# DD2090_4CAM_FFC_MIPI_2LANE_CAM.net
KiCad netlist of a schematic drawn in Altium Designer
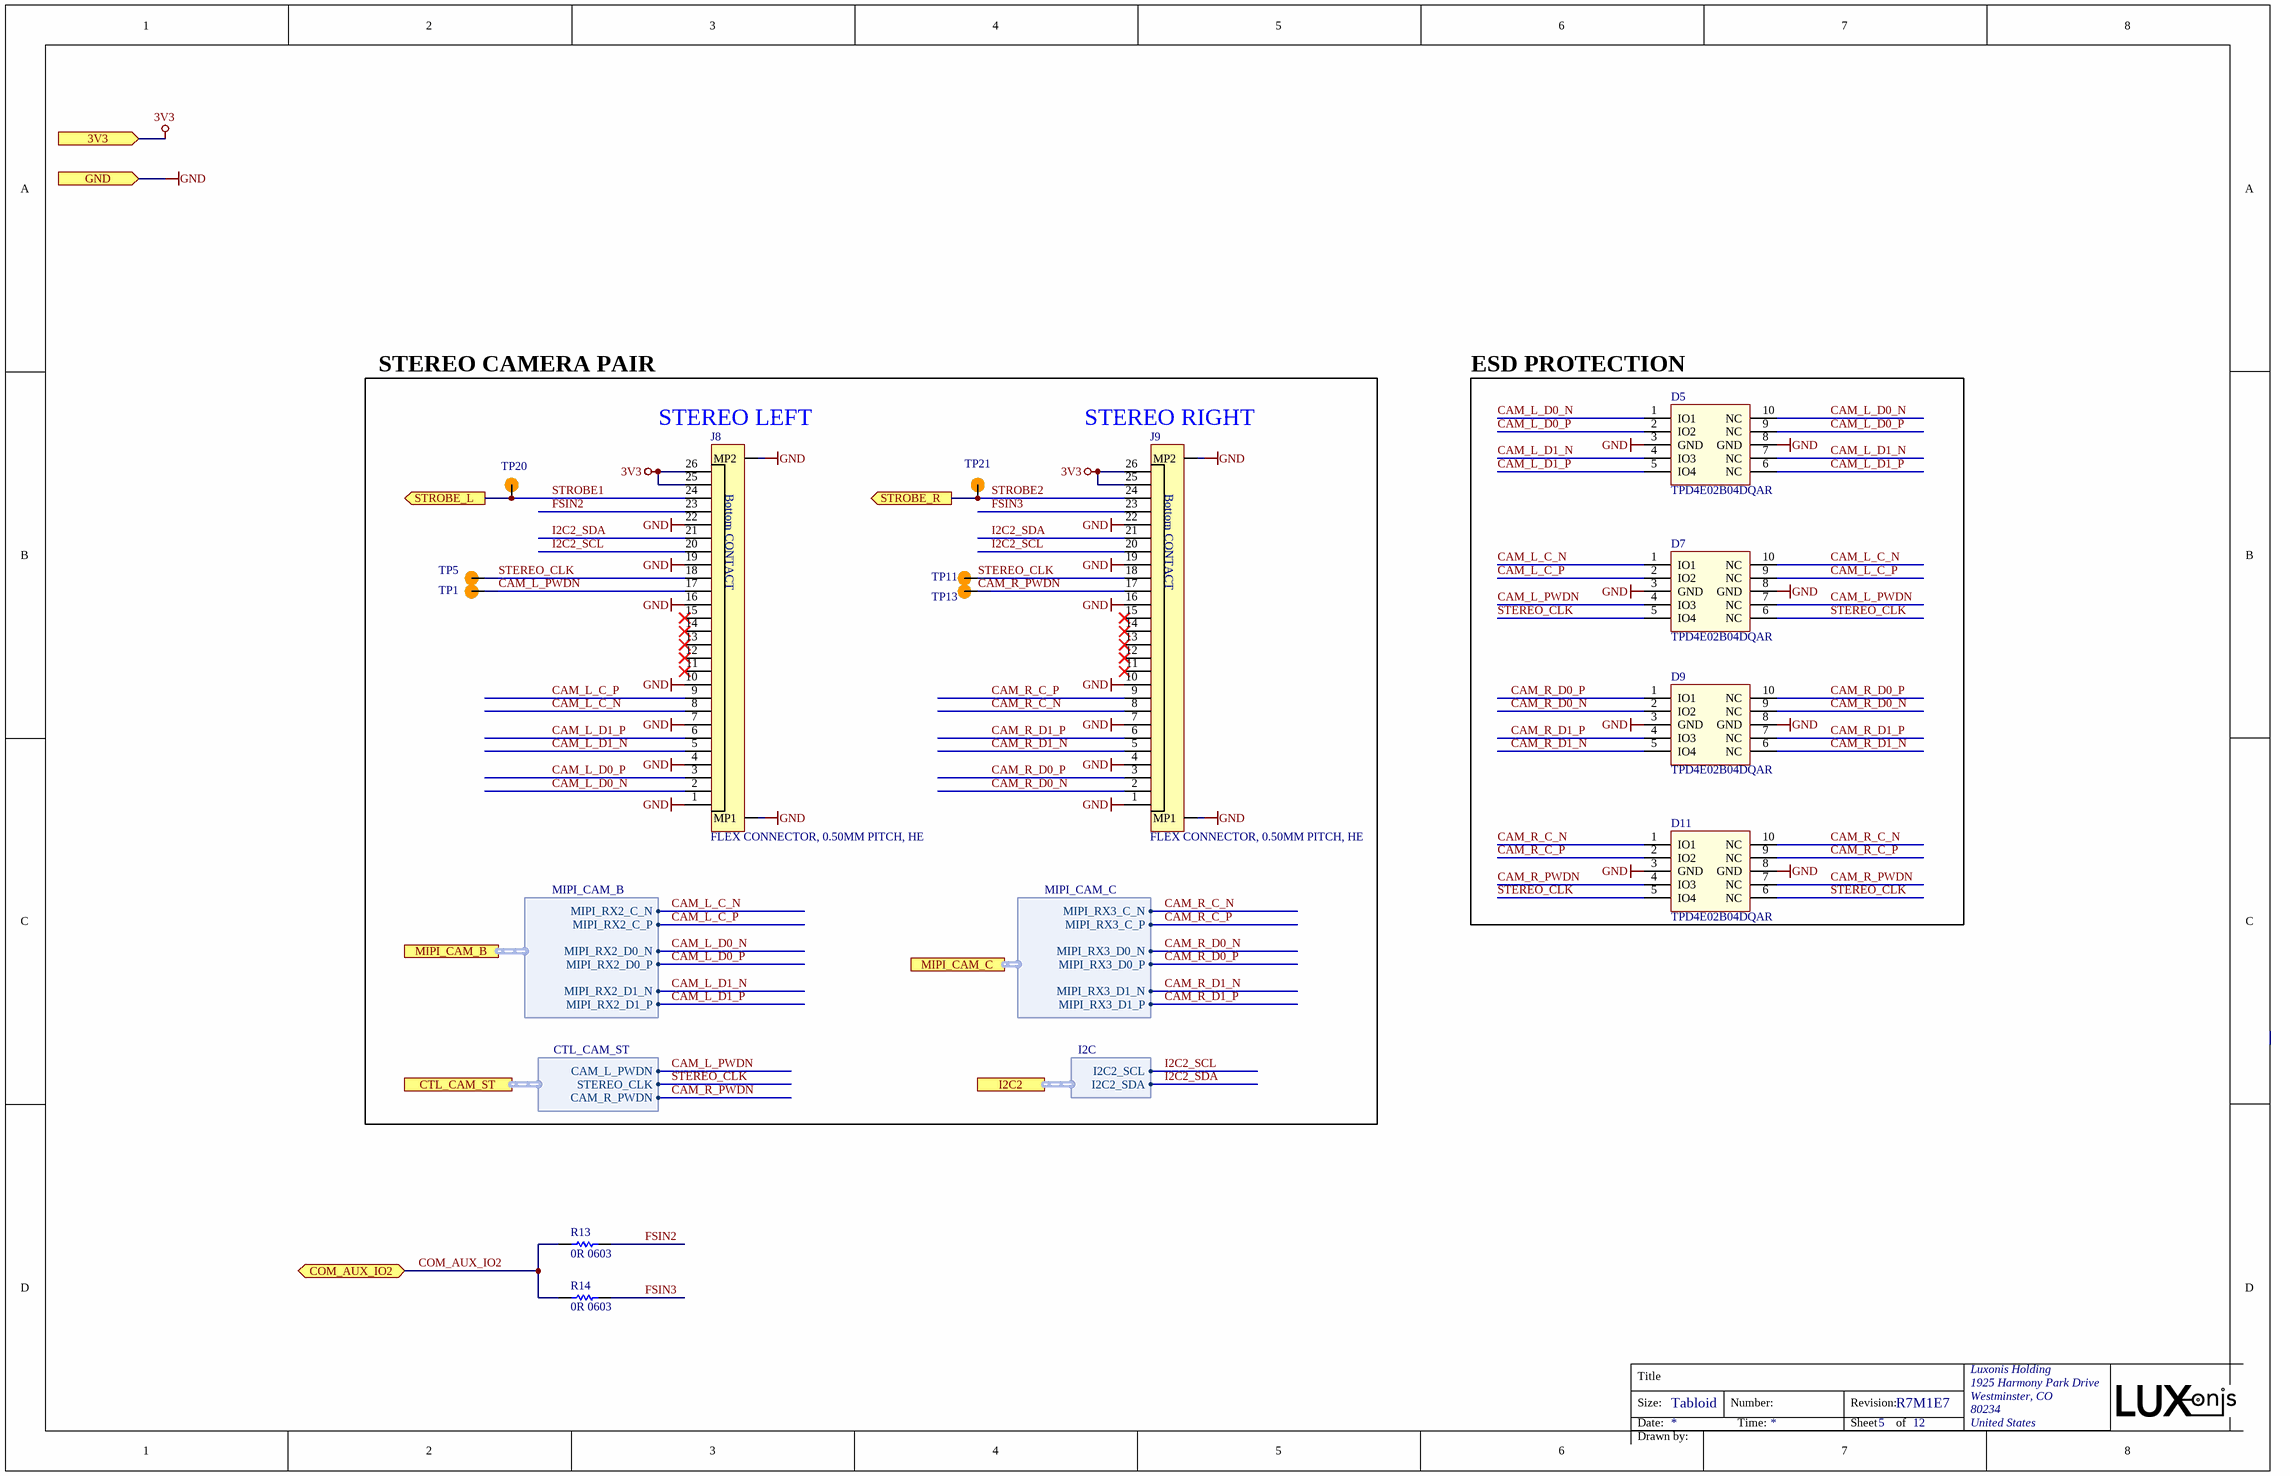
[diagram p0: DD2090_4CAM_FFC_MIPI_2LANE_CAM.SchDoc]

(export (version "E")
  (design (tool "Eeschema 10.0.6"))
  (components
    (comp (ref "D5")
      (value "TPD4E02B04DQAR")
      (footprint "LuxonisMaster:TPD4E02B04DQAR")
      (libsource (lib "LuxonisMaster") (part "TPD4E02B04DQAR"))
    )
    (comp (ref "D7")
      (value "TPD4E02B04DQAR")
      (footprint "LuxonisMaster:TPD4E02B04DQAR")
      (libsource (lib "LuxonisMaster") (part "TPD4E02B04DQAR"))
    )
    (comp (ref "D9")
      (value "TPD4E02B04DQAR")
      (footprint "LuxonisMaster:TPD4E02B04DQAR")
      (libsource (lib "LuxonisMaster") (part "TPD4E02B04DQAR"))
    )
    (comp (ref "D11")
      (value "TPD4E02B04DQAR")
      (footprint "LuxonisMaster:TPD4E02B04DQAR")
      (libsource (lib "LuxonisMaster") (part "TPD4E02B04DQAR"))
    )
    (comp (ref "J8")
      (value "FLEX CONNECTOR, 0.50MM PITCH, HE")
      (footprint "DM1090FFC:F32R-1A7H1-11026")
      (description "26 Position FFC, FPC Connector Contacts, Bottom 0.020\" (0.50mm) Surface Mount, Right Angle")
      (libsource (lib "DM1090FFC") (part "F32R-1A7H1-11026"))
    )
    (comp (ref "J9")
      (value "FLEX CONNECTOR, 0.50MM PITCH, HE")
      (footprint "DM1090FFC:F32R-1A7H1-11026")
      (description "26 Position FFC, FPC Connector Contacts, Bottom 0.020\" (0.50mm) Surface Mount, Right Angle")
      (libsource (lib "DM1090FFC") (part "F32R-1A7H1-11026"))
    )
    (comp (ref "R13")
      (value "0R 0603")
      (footprint "RES_Altium_Vault_Generic:RESC0603(1608)_N")
      (fields (field (name "TOLERANCE") "5%"))
      (libsource (lib "LuxonisMaster") (part "CRCW06030000Z0EA"))
    )
    (comp (ref "R14")
      (value "0R 0603")
      (footprint "RES_Altium_Vault_Generic:RESC0603(1608)_N")
      (fields (field (name "TOLERANCE") "5%"))
      (libsource (lib "LuxonisMaster") (part "CRCW06030000Z0EA"))
    )
    (comp (ref "TP1")
      (value "TP100_200_NS")
      (footprint "LuxonisMaster:TP100_200_NS")
      (libsource (lib "LuxonisMaster") (part "TEST_POINT"))
    )
    (comp (ref "TP5")
      (value "TP100_200_NS")
      (footprint "LuxonisMaster:TP100_200_NS")
      (libsource (lib "LuxonisMaster") (part "TEST_POINT"))
    )
    (comp (ref "TP11")
      (value "TP100_200_NS")
      (footprint "LuxonisMaster:TP100_200_NS")
      (libsource (lib "LuxonisMaster") (part "TEST_POINT"))
    )
    (comp (ref "TP13")
      (value "TP100_200_NS")
      (footprint "LuxonisMaster:TP100_200_NS")
      (libsource (lib "LuxonisMaster") (part "TEST_POINT"))
    )
    (comp (ref "TP20")
      (value "TP100_200_NS")
      (footprint "LuxonisMaster:TP100_200_NS")
      (libsource (lib "LuxonisMaster") (part "TEST_POINT"))
    )
    (comp (ref "TP21")
      (value "TP100_200_NS")
      (footprint "LuxonisMaster:TP100_200_NS")
      (libsource (lib "LuxonisMaster") (part "TEST_POINT"))
    )
  )
  (nets
    (net (code "5") (name "/CAM_L_C_N") (class "Default")
      (node (ref "D7") (pin "1") (pinfunction "IO1_1") (pintype "passive"))
      (node (ref "D7") (pin "10") (pinfunction "NC_10") (pintype "passive"))
      (node (ref "J8") (pin "8") (pinfunction "8_8") (pintype "passive"))
    )
    (net (code "6") (name "/CAM_L_C_P") (class "Default")
      (node (ref "D7") (pin "2") (pinfunction "IO2_2") (pintype "passive"))
      (node (ref "D7") (pin "9") (pinfunction "NC_9") (pintype "passive"))
      (node (ref "J8") (pin "9") (pinfunction "9_9") (pintype "passive"))
    )
    (net (code "7") (name "/CAM_L_D0_N") (class "Default")
      (node (ref "D5") (pin "1") (pinfunction "IO1_1") (pintype "passive"))
      (node (ref "D5") (pin "10") (pinfunction "NC_10") (pintype "passive"))
      (node (ref "J8") (pin "2") (pinfunction "2_2") (pintype "passive"))
    )
    (net (code "8") (name "/CAM_L_D0_P") (class "Default")
      (node (ref "D5") (pin "2") (pinfunction "IO2_2") (pintype "passive"))
      (node (ref "D5") (pin "9") (pinfunction "NC_9") (pintype "passive"))
      (node (ref "J8") (pin "3") (pinfunction "3_3") (pintype "passive"))
    )
    (net (code "9") (name "/CAM_L_D1_N") (class "Default")
      (node (ref "D5") (pin "4") (pinfunction "IO3_4") (pintype "passive"))
      (node (ref "D5") (pin "7") (pinfunction "NC_7") (pintype "passive"))
      (node (ref "J8") (pin "5") (pinfunction "5_5") (pintype "passive"))
    )
    (net (code "10") (name "/CAM_L_D1_P") (class "Default")
      (node (ref "D5") (pin "5") (pinfunction "IO4_5") (pintype "passive"))
      (node (ref "D5") (pin "6") (pinfunction "NC_6") (pintype "passive"))
      (node (ref "J8") (pin "6") (pinfunction "6_6") (pintype "passive"))
    )
    (net (code "11") (name "/CAM_L_PWDN") (class "Default")
      (node (ref "D7") (pin "4") (pinfunction "IO3_4") (pintype "passive"))
      (node (ref "D7") (pin "7") (pinfunction "NC_7") (pintype "passive"))
      (node (ref "J8") (pin "17") (pinfunction "17_17") (pintype "passive"))
      (node (ref "TP1") (pin "1") (pintype "passive"))
    )
    (net (code "12") (name "/CAM_R_C_N") (class "Default")
      (node (ref "D11") (pin "1") (pinfunction "IO1_1") (pintype "passive"))
      (node (ref "D11") (pin "10") (pinfunction "NC_10") (pintype "passive"))
      (node (ref "J9") (pin "8") (pinfunction "8_8") (pintype "passive"))
    )
    (net (code "13") (name "/CAM_R_C_P") (class "Default")
      (node (ref "D11") (pin "2") (pinfunction "IO2_2") (pintype "passive"))
      (node (ref "D11") (pin "9") (pinfunction "NC_9") (pintype "passive"))
      (node (ref "J9") (pin "9") (pinfunction "9_9") (pintype "passive"))
    )
    (net (code "14") (name "/CAM_R_D0_N") (class "Default")
      (node (ref "D9") (pin "2") (pinfunction "IO2_2") (pintype "passive"))
      (node (ref "D9") (pin "9") (pinfunction "NC_9") (pintype "passive"))
      (node (ref "J9") (pin "2") (pinfunction "2_2") (pintype "passive"))
    )
    (net (code "15") (name "/CAM_R_D0_P") (class "Default")
      (node (ref "D9") (pin "1") (pinfunction "IO1_1") (pintype "passive"))
      (node (ref "D9") (pin "10") (pinfunction "NC_10") (pintype "passive"))
      (node (ref "J9") (pin "3") (pinfunction "3_3") (pintype "passive"))
    )
    (net (code "16") (name "/CAM_R_D1_N") (class "Default")
      (node (ref "D9") (pin "5") (pinfunction "IO4_5") (pintype "passive"))
      (node (ref "D9") (pin "6") (pinfunction "NC_6") (pintype "passive"))
      (node (ref "J9") (pin "5") (pinfunction "5_5") (pintype "passive"))
    )
    (net (code "17") (name "/CAM_R_D1_P") (class "Default")
      (node (ref "D9") (pin "4") (pinfunction "IO3_4") (pintype "passive"))
      (node (ref "D9") (pin "7") (pinfunction "NC_7") (pintype "passive"))
      (node (ref "J9") (pin "6") (pinfunction "6_6") (pintype "passive"))
    )
    (net (code "18") (name "/CAM_R_PWDN") (class "Default")
      (node (ref "D11") (pin "4") (pinfunction "IO3_4") (pintype "passive"))
      (node (ref "D11") (pin "7") (pinfunction "NC_7") (pintype "passive"))
      (node (ref "J9") (pin "17") (pinfunction "17_17") (pintype "passive"))
      (node (ref "TP13") (pin "1") (pintype "passive"))
    )
    (net (code "19") (name "/COM_AUX_IO2") (class "Default")
      (node (ref "R13") (pin "1") (pinfunction "1_1") (pintype "passive"))
      (node (ref "R14") (pin "1") (pinfunction "1_1") (pintype "passive"))
    )
    (net (code "20") (name "/FSIN2") (class "Default")
      (node (ref "J8") (pin "23") (pinfunction "23_23") (pintype "passive"))
      (node (ref "R13") (pin "2") (pinfunction "2_2") (pintype "passive"))
    )
    (net (code "21") (name "/FSIN3") (class "Default")
      (node (ref "J9") (pin "23") (pinfunction "23_23") (pintype "passive"))
      (node (ref "R14") (pin "2") (pinfunction "2_2") (pintype "passive"))
    )
    (net (code "22") (name "/I2C2_SCL") (class "Default")
      (node (ref "J8") (pin "20") (pinfunction "20_20") (pintype "passive"))
      (node (ref "J9") (pin "20") (pinfunction "20_20") (pintype "passive"))
    )
    (net (code "23") (name "/I2C2_SDA") (class "Default")
      (node (ref "J8") (pin "21") (pinfunction "21_21") (pintype "passive"))
      (node (ref "J9") (pin "21") (pinfunction "21_21") (pintype "passive"))
    )
    (net (code "24") (name "/STEREO_CLK") (class "Default")
      (node (ref "D11") (pin "5") (pinfunction "IO4_5") (pintype "passive"))
      (node (ref "D11") (pin "6") (pinfunction "NC_6") (pintype "passive"))
      (node (ref "D7") (pin "5") (pinfunction "IO4_5") (pintype "passive"))
      (node (ref "D7") (pin "6") (pinfunction "NC_6") (pintype "passive"))
      (node (ref "J8") (pin "18") (pinfunction "18_18") (pintype "passive"))
      (node (ref "J9") (pin "18") (pinfunction "18_18") (pintype "passive"))
      (node (ref "TP11") (pin "1") (pintype "passive"))
      (node (ref "TP5") (pin "1") (pintype "passive"))
    )
    (net (code "25") (name "/STROBE1") (class "Default")
      (node (ref "J8") (pin "24") (pinfunction "24_24") (pintype "passive"))
      (node (ref "TP20") (pin "1") (pintype "passive"))
    )
    (net (code "26") (name "/STROBE2") (class "Default")
      (node (ref "J9") (pin "24") (pinfunction "24_24") (pintype "passive"))
      (node (ref "TP21") (pin "1") (pintype "passive"))
    )
    (net (code "31") (name "3V3") (class "Default")
      (node (ref "J8") (pin "25") (pinfunction "25_25") (pintype "passive"))
      (node (ref "J8") (pin "26") (pinfunction "26_26") (pintype "passive"))
      (node (ref "J9") (pin "25") (pinfunction "25_25") (pintype "passive"))
      (node (ref "J9") (pin "26") (pinfunction "26_26") (pintype "passive"))
    )
    (net (code "32") (name "GND") (class "Default")
      (node (ref "D11") (pin "3") (pinfunction "GND_3") (pintype "passive"))
      (node (ref "D11") (pin "8") (pinfunction "GND_8") (pintype "passive"))
      (node (ref "D5") (pin "3") (pinfunction "GND_3") (pintype "passive"))
      (node (ref "D5") (pin "8") (pinfunction "GND_8") (pintype "passive"))
      (node (ref "D7") (pin "3") (pinfunction "GND_3") (pintype "passive"))
      (node (ref "D7") (pin "8") (pinfunction "GND_8") (pintype "passive"))
      (node (ref "D9") (pin "3") (pinfunction "GND_3") (pintype "passive"))
      (node (ref "D9") (pin "8") (pinfunction "GND_8") (pintype "passive"))
      (node (ref "J8") (pin "1") (pinfunction "1_1") (pintype "passive"))
      (node (ref "J8") (pin "10") (pinfunction "10_10") (pintype "passive"))
      (node (ref "J8") (pin "16") (pinfunction "16_16") (pintype "passive"))
      (node (ref "J8") (pin "19") (pinfunction "19_19") (pintype "passive"))
      (node (ref "J8") (pin "22") (pinfunction "22_22") (pintype "passive"))
      (node (ref "J8") (pin "4") (pinfunction "4_4") (pintype "passive"))
      (node (ref "J8") (pin "7") (pinfunction "7_7") (pintype "passive"))
      (node (ref "J8") (pin "MP1") (pinfunction "MP1_MP1") (pintype "passive"))
      (node (ref "J8") (pin "MP2") (pinfunction "MP2_MP2") (pintype "passive"))
      (node (ref "J9") (pin "1") (pinfunction "1_1") (pintype "passive"))
      (node (ref "J9") (pin "10") (pinfunction "10_10") (pintype "passive"))
      (node (ref "J9") (pin "16") (pinfunction "16_16") (pintype "passive"))
      (node (ref "J9") (pin "19") (pinfunction "19_19") (pintype "passive"))
      (node (ref "J9") (pin "22") (pinfunction "22_22") (pintype "passive"))
      (node (ref "J9") (pin "4") (pinfunction "4_4") (pintype "passive"))
      (node (ref "J9") (pin "7") (pinfunction "7_7") (pintype "passive"))
      (node (ref "J9") (pin "MP1") (pinfunction "MP1_MP1") (pintype "passive"))
      (node (ref "J9") (pin "MP2") (pinfunction "MP2_MP2") (pintype "passive"))
    )
    (net (code "33") (name "unconnected-(J8-Pad11)") (class "Default")
      (node (ref "J8") (pin "11") (pinfunction "11_11") (pintype "passive+no_connect"))
    )
    (net (code "34") (name "unconnected-(J8-Pad12)") (class "Default")
      (node (ref "J8") (pin "12") (pinfunction "12_12") (pintype "passive+no_connect"))
    )
    (net (code "35") (name "unconnected-(J8-Pad13)") (class "Default")
      (node (ref "J8") (pin "13") (pinfunction "13_13") (pintype "passive+no_connect"))
    )
    (net (code "36") (name "unconnected-(J8-Pad14)") (class "Default")
      (node (ref "J8") (pin "14") (pinfunction "14_14") (pintype "passive+no_connect"))
    )
    (net (code "37") (name "unconnected-(J8-Pad15)") (class "Default")
      (node (ref "J8") (pin "15") (pinfunction "15_15") (pintype "passive+no_connect"))
    )
    (net (code "38") (name "unconnected-(J9-Pad11)") (class "Default")
      (node (ref "J9") (pin "11") (pinfunction "11_11") (pintype "passive+no_connect"))
    )
    (net (code "39") (name "unconnected-(J9-Pad12)") (class "Default")
      (node (ref "J9") (pin "12") (pinfunction "12_12") (pintype "passive+no_connect"))
    )
    (net (code "40") (name "unconnected-(J9-Pad13)") (class "Default")
      (node (ref "J9") (pin "13") (pinfunction "13_13") (pintype "passive+no_connect"))
    )
    (net (code "41") (name "unconnected-(J9-Pad14)") (class "Default")
      (node (ref "J9") (pin "14") (pinfunction "14_14") (pintype "passive+no_connect"))
    )
    (net (code "42") (name "unconnected-(J9-Pad15)") (class "Default")
      (node (ref "J9") (pin "15") (pinfunction "15_15") (pintype "passive+no_connect"))
    )
  )
)
